# brushless_motorshield_v1.net
KiCad netlist of a schematic drawn in EAGLE
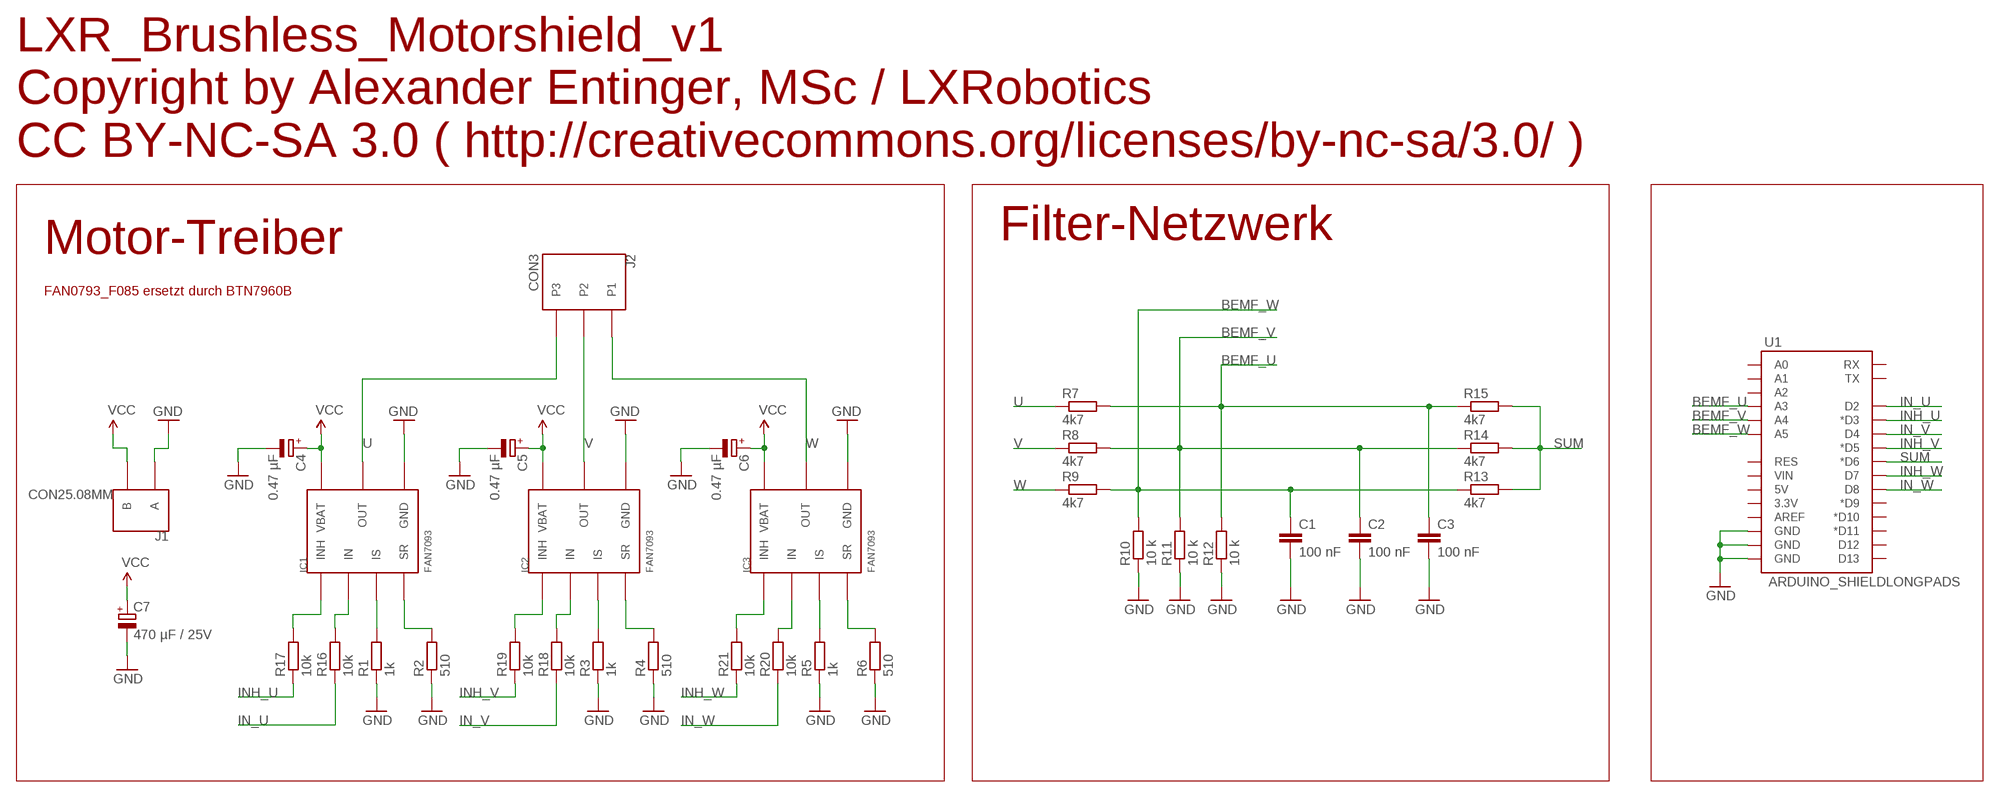
[diagram p0: schematic, sheet 1]

(export (version "E")
  (design (tool "Eeschema 10.0.6"))
  (components
    (comp (ref "C1")
      (value "100 nF")
      (footprint "eagle-import:C0805")
      (libsource (lib "eagle-import") (part "C-EUC0805"))
    )
    (comp (ref "C2")
      (value "100 nF")
      (footprint "eagle-import:C0805")
      (libsource (lib "eagle-import") (part "C-EUC0805"))
    )
    (comp (ref "C3")
      (value "100 nF")
      (footprint "eagle-import:C0805")
      (libsource (lib "eagle-import") (part "C-EUC0805"))
    )
    (comp (ref "C4")
      (value "0.47 µF")
      (footprint "eagle-import:KEMET_A")
      (libsource (lib "eagle-import") (part "CPOL-EU"))
    )
    (comp (ref "C5")
      (value "0.47 µF")
      (footprint "eagle-import:KEMET_A")
      (libsource (lib "eagle-import") (part "CPOL-EU"))
    )
    (comp (ref "C6")
      (value "0.47 µF")
      (footprint "eagle-import:KEMET_A")
      (libsource (lib "eagle-import") (part "CPOL-EU"))
    )
    (comp (ref "C7")
      (value "470 µF / 25V")
      (footprint "eagle-import:E5-10,5")
      (libsource (lib "eagle-import") (part "CPOL-EUE5-10.5"))
    )
    (comp (ref "IC1")
      (value "FAN7093")
      (footprint "eagle-import:TO263-7L")
      (libsource (lib "eagle-import") (part "FAN7093"))
    )
    (comp (ref "IC2")
      (value "FAN7093")
      (footprint "eagle-import:TO263-7L")
      (libsource (lib "eagle-import") (part "FAN7093"))
    )
    (comp (ref "IC3")
      (value "FAN7093")
      (footprint "eagle-import:TO263-7L")
      (libsource (lib "eagle-import") (part "FAN7093"))
    )
    (comp (ref "J1")
      (value "CON25.08MM")
      (footprint "eagle-import:CON2_SCHRAUBKLEMME")
      (libsource (lib "eagle-import") (part "CON25.08MM"))
    )
    (comp (ref "J2")
      (value "CON3")
      (footprint "eagle-import:CON3_SCHRAUBKLEMME")
      (libsource (lib "eagle-import") (part "CON3"))
    )
    (comp (ref "R1")
      (value "1k")
      (footprint "eagle-import:R0805")
      (libsource (lib "eagle-import") (part "R-EU_R0805"))
    )
    (comp (ref "R2")
      (value "510")
      (footprint "eagle-import:R0805")
      (libsource (lib "eagle-import") (part "R-EU_R0805"))
    )
    (comp (ref "R3")
      (value "1k")
      (footprint "eagle-import:R0805")
      (libsource (lib "eagle-import") (part "R-EU_R0805"))
    )
    (comp (ref "R4")
      (value "510")
      (footprint "eagle-import:R0805")
      (libsource (lib "eagle-import") (part "R-EU_R0805"))
    )
    (comp (ref "R5")
      (value "1k")
      (footprint "eagle-import:R0805")
      (libsource (lib "eagle-import") (part "R-EU_R0805"))
    )
    (comp (ref "R6")
      (value "510")
      (footprint "eagle-import:R0805")
      (libsource (lib "eagle-import") (part "R-EU_R0805"))
    )
    (comp (ref "R7")
      (value "4k7")
      (footprint "eagle-import:R0805")
      (libsource (lib "eagle-import") (part "R-EU_R0805"))
    )
    (comp (ref "R8")
      (value "4k7")
      (footprint "eagle-import:R0805")
      (libsource (lib "eagle-import") (part "R-EU_R0805"))
    )
    (comp (ref "R9")
      (value "4k7")
      (footprint "eagle-import:R0805")
      (libsource (lib "eagle-import") (part "R-EU_R0805"))
    )
    (comp (ref "R10")
      (value "10 k")
      (footprint "eagle-import:R0805")
      (libsource (lib "eagle-import") (part "R-EU_R0805"))
    )
    (comp (ref "R11")
      (value "10 k")
      (footprint "eagle-import:R0805")
      (libsource (lib "eagle-import") (part "R-EU_R0805"))
    )
    (comp (ref "R12")
      (value "10 k")
      (footprint "eagle-import:R0805")
      (libsource (lib "eagle-import") (part "R-EU_R0805"))
    )
    (comp (ref "R13")
      (value "4k7")
      (footprint "eagle-import:R0805")
      (libsource (lib "eagle-import") (part "R-EU_R0805"))
    )
    (comp (ref "R14")
      (value "4k7")
      (footprint "eagle-import:R0805")
      (libsource (lib "eagle-import") (part "R-EU_R0805"))
    )
    (comp (ref "R15")
      (value "4k7")
      (footprint "eagle-import:R0805")
      (libsource (lib "eagle-import") (part "R-EU_R0805"))
    )
    (comp (ref "R16")
      (value "10k")
      (footprint "eagle-import:R0805")
      (libsource (lib "eagle-import") (part "R-EU_R0805"))
    )
    (comp (ref "R17")
      (value "10k")
      (footprint "eagle-import:R0805")
      (libsource (lib "eagle-import") (part "R-EU_R0805"))
    )
    (comp (ref "R18")
      (value "10k")
      (footprint "eagle-import:R0805")
      (libsource (lib "eagle-import") (part "R-EU_R0805"))
    )
    (comp (ref "R19")
      (value "10k")
      (footprint "eagle-import:R0805")
      (libsource (lib "eagle-import") (part "R-EU_R0805"))
    )
    (comp (ref "R20")
      (value "10k")
      (footprint "eagle-import:R0805")
      (libsource (lib "eagle-import") (part "R-EU_R0805"))
    )
    (comp (ref "R21")
      (value "10k")
      (footprint "eagle-import:R0805")
      (libsource (lib "eagle-import") (part "R-EU_R0805"))
    )
    (comp (ref "U1")
      (value "ARDUINO_SHIELDLONGPADS")
      (footprint "eagle-import:DUEMILANOVE_SHIELD_LONGPADS")
      (libsource (lib "eagle-import") (part "ARDUINO_SHIELDLONGPADS"))
    )
  )
  (nets
    (net (code "1") (name "/BEMF_U") (class "Default")
      (node (ref "C3") (pin "1") (pinfunction "1_1") (pintype "passive"))
      (node (ref "R12") (pin "2") (pinfunction "2_2") (pintype "passive"))
      (node (ref "R15") (pin "1") (pinfunction "1_1") (pintype "passive"))
      (node (ref "R7") (pin "2") (pinfunction "2_2") (pintype "passive"))
      (node (ref "U1") (pin "A3") (pinfunction "A3_A3") (pintype "bidirectional"))
    )
    (net (code "2") (name "/BEMF_V") (class "Default")
      (node (ref "C2") (pin "1") (pinfunction "1_1") (pintype "passive"))
      (node (ref "R11") (pin "2") (pinfunction "2_2") (pintype "passive"))
      (node (ref "R14") (pin "1") (pinfunction "1_1") (pintype "passive"))
      (node (ref "R8") (pin "2") (pinfunction "2_2") (pintype "passive"))
      (node (ref "U1") (pin "A4") (pinfunction "A4_A4") (pintype "bidirectional"))
    )
    (net (code "3") (name "/BEMF_W") (class "Default")
      (node (ref "C1") (pin "1") (pinfunction "1_1") (pintype "passive"))
      (node (ref "R10") (pin "2") (pinfunction "2_2") (pintype "passive"))
      (node (ref "R13") (pin "1") (pinfunction "1_1") (pintype "passive"))
      (node (ref "R9") (pin "2") (pinfunction "2_2") (pintype "passive"))
      (node (ref "U1") (pin "A5") (pinfunction "A5_A5") (pintype "bidirectional"))
    )
    (net (code "4") (name "/INH_U") (class "Default")
      (node (ref "R17") (pin "1") (pinfunction "1_1") (pintype "passive"))
      (node (ref "U1") (pin "D3") (pinfunction "*D3_D3") (pintype "bidirectional"))
    )
    (net (code "5") (name "/INH_V") (class "Default")
      (node (ref "R19") (pin "1") (pinfunction "1_1") (pintype "passive"))
      (node (ref "U1") (pin "D5") (pinfunction "*D5_D5") (pintype "bidirectional"))
    )
    (net (code "6") (name "/INH_W") (class "Default")
      (node (ref "R21") (pin "1") (pinfunction "1_1") (pintype "passive"))
      (node (ref "U1") (pin "D7") (pinfunction "D7_D7") (pintype "bidirectional"))
    )
    (net (code "7") (name "/IN_U") (class "Default")
      (node (ref "R16") (pin "1") (pinfunction "1_1") (pintype "passive"))
      (node (ref "U1") (pin "D2") (pinfunction "D2_D2") (pintype "bidirectional"))
    )
    (net (code "8") (name "/IN_V") (class "Default")
      (node (ref "R18") (pin "1") (pinfunction "1_1") (pintype "passive"))
      (node (ref "U1") (pin "D4") (pinfunction "D4_D4") (pintype "bidirectional"))
    )
    (net (code "9") (name "/IN_W") (class "Default")
      (node (ref "R20") (pin "1") (pinfunction "1_1") (pintype "passive"))
      (node (ref "U1") (pin "D8") (pinfunction "D8_D8") (pintype "bidirectional"))
    )
    (net (code "10") (name "/SUM") (class "Default")
      (node (ref "R13") (pin "2") (pinfunction "2_2") (pintype "passive"))
      (node (ref "R14") (pin "2") (pinfunction "2_2") (pintype "passive"))
      (node (ref "R15") (pin "2") (pinfunction "2_2") (pintype "passive"))
      (node (ref "U1") (pin "D6") (pinfunction "*D6_D6") (pintype "bidirectional"))
    )
    (net (code "11") (name "/U") (class "Default")
      (node (ref "IC1") (pin "OUT") (pinfunction "OUT_OUT") (pintype "bidirectional"))
      (node (ref "IC1") (pin "OUT@1") (pinfunction "OUT_OUT@1") (pintype "bidirectional"))
      (node (ref "J2") (pin "P3") (pinfunction "P3_P3") (pintype "bidirectional"))
      (node (ref "R7") (pin "1") (pinfunction "1_1") (pintype "passive"))
    )
    (net (code "12") (name "/V") (class "Default")
      (node (ref "IC2") (pin "OUT") (pinfunction "OUT_OUT") (pintype "bidirectional"))
      (node (ref "IC2") (pin "OUT@1") (pinfunction "OUT_OUT@1") (pintype "bidirectional"))
      (node (ref "J2") (pin "P2") (pinfunction "P2_P2") (pintype "bidirectional"))
      (node (ref "R8") (pin "1") (pinfunction "1_1") (pintype "passive"))
    )
    (net (code "13") (name "/W") (class "Default")
      (node (ref "IC3") (pin "OUT") (pinfunction "OUT_OUT") (pintype "bidirectional"))
      (node (ref "IC3") (pin "OUT@1") (pinfunction "OUT_OUT@1") (pintype "bidirectional"))
      (node (ref "J2") (pin "P1") (pinfunction "P1_P1") (pintype "bidirectional"))
      (node (ref "R9") (pin "1") (pinfunction "1_1") (pintype "passive"))
    )
    (net (code "14") (name "GND") (class "Default")
      (node (ref "C1") (pin "2") (pinfunction "2_2") (pintype "passive"))
      (node (ref "C2") (pin "2") (pinfunction "2_2") (pintype "passive"))
      (node (ref "C3") (pin "2") (pinfunction "2_2") (pintype "passive"))
      (node (ref "C4") (pin "CATHODE") (pinfunction "-_CATHODE") (pintype "passive"))
      (node (ref "C5") (pin "CATHODE") (pinfunction "-_CATHODE") (pintype "passive"))
      (node (ref "C6") (pin "CATHODE") (pinfunction "-_CATHODE") (pintype "passive"))
      (node (ref "C7") (pin "-") (pinfunction "-_-") (pintype "passive"))
      (node (ref "IC1") (pin "GND") (pinfunction "GND_GND") (pintype "bidirectional"))
      (node (ref "IC2") (pin "GND") (pinfunction "GND_GND") (pintype "bidirectional"))
      (node (ref "IC3") (pin "GND") (pinfunction "GND_GND") (pintype "bidirectional"))
      (node (ref "J1") (pin "1") (pinfunction "A_1") (pintype "bidirectional"))
      (node (ref "R1") (pin "1") (pinfunction "1_1") (pintype "passive"))
      (node (ref "R10") (pin "1") (pinfunction "1_1") (pintype "passive"))
      (node (ref "R11") (pin "1") (pinfunction "1_1") (pintype "passive"))
      (node (ref "R12") (pin "1") (pinfunction "1_1") (pintype "passive"))
      (node (ref "R2") (pin "1") (pinfunction "1_1") (pintype "passive"))
      (node (ref "R3") (pin "1") (pinfunction "1_1") (pintype "passive"))
      (node (ref "R4") (pin "1") (pinfunction "1_1") (pintype "passive"))
      (node (ref "R5") (pin "1") (pinfunction "1_1") (pintype "passive"))
      (node (ref "R6") (pin "1") (pinfunction "1_1") (pintype "passive"))
      (node (ref "U1") (pin "GND@0") (pinfunction "GND_GND@0") (pintype "bidirectional"))
      (node (ref "U1") (pin "GND@1") (pinfunction "GND_GND@1") (pintype "bidirectional"))
      (node (ref "U1") (pin "GND@2") (pinfunction "GND_GND@2") (pintype "bidirectional"))
    )
    (net (code "15") (name "Net-(IC1-PadIN)") (class "Default")
      (node (ref "IC1") (pin "IN") (pinfunction "IN_IN") (pintype "bidirectional"))
      (node (ref "R16") (pin "2") (pinfunction "2_2") (pintype "passive"))
    )
    (net (code "16") (name "Net-(IC1-PadINH)") (class "Default")
      (node (ref "IC1") (pin "INH") (pinfunction "INH_INH") (pintype "bidirectional"))
      (node (ref "R17") (pin "2") (pinfunction "2_2") (pintype "passive"))
    )
    (net (code "17") (name "Net-(IC1-PadIS)") (class "Default")
      (node (ref "IC1") (pin "IS") (pinfunction "IS_IS") (pintype "bidirectional"))
      (node (ref "R1") (pin "2") (pinfunction "2_2") (pintype "passive"))
    )
    (net (code "18") (name "Net-(IC1-PadSR)") (class "Default")
      (node (ref "IC1") (pin "SR") (pinfunction "SR_SR") (pintype "bidirectional"))
      (node (ref "R2") (pin "2") (pinfunction "2_2") (pintype "passive"))
    )
    (net (code "19") (name "Net-(IC2-PadIN)") (class "Default")
      (node (ref "IC2") (pin "IN") (pinfunction "IN_IN") (pintype "bidirectional"))
      (node (ref "R18") (pin "2") (pinfunction "2_2") (pintype "passive"))
    )
    (net (code "20") (name "Net-(IC2-PadINH)") (class "Default")
      (node (ref "IC2") (pin "INH") (pinfunction "INH_INH") (pintype "bidirectional"))
      (node (ref "R19") (pin "2") (pinfunction "2_2") (pintype "passive"))
    )
    (net (code "21") (name "Net-(IC2-PadIS)") (class "Default")
      (node (ref "IC2") (pin "IS") (pinfunction "IS_IS") (pintype "bidirectional"))
      (node (ref "R3") (pin "2") (pinfunction "2_2") (pintype "passive"))
    )
    (net (code "22") (name "Net-(IC2-PadSR)") (class "Default")
      (node (ref "IC2") (pin "SR") (pinfunction "SR_SR") (pintype "bidirectional"))
      (node (ref "R4") (pin "2") (pinfunction "2_2") (pintype "passive"))
    )
    (net (code "23") (name "Net-(IC3-PadIN)") (class "Default")
      (node (ref "IC3") (pin "IN") (pinfunction "IN_IN") (pintype "bidirectional"))
      (node (ref "R20") (pin "2") (pinfunction "2_2") (pintype "passive"))
    )
    (net (code "24") (name "Net-(IC3-PadINH)") (class "Default")
      (node (ref "IC3") (pin "INH") (pinfunction "INH_INH") (pintype "bidirectional"))
      (node (ref "R21") (pin "2") (pinfunction "2_2") (pintype "passive"))
    )
    (net (code "25") (name "Net-(IC3-PadIS)") (class "Default")
      (node (ref "IC3") (pin "IS") (pinfunction "IS_IS") (pintype "bidirectional"))
      (node (ref "R5") (pin "2") (pinfunction "2_2") (pintype "passive"))
    )
    (net (code "26") (name "Net-(IC3-PadSR)") (class "Default")
      (node (ref "IC3") (pin "SR") (pinfunction "SR_SR") (pintype "bidirectional"))
      (node (ref "R6") (pin "2") (pinfunction "2_2") (pintype "passive"))
    )
    (net (code "27") (name "VCC") (class "Default")
      (node (ref "C4") (pin "ANODE") (pinfunction "+_ANODE") (pintype "passive"))
      (node (ref "C5") (pin "ANODE") (pinfunction "+_ANODE") (pintype "passive"))
      (node (ref "C6") (pin "ANODE") (pinfunction "+_ANODE") (pintype "passive"))
      (node (ref "C7") (pin "+") (pinfunction "+_+") (pintype "passive"))
      (node (ref "IC1") (pin "VBATT") (pinfunction "VBAT_VBATT") (pintype "bidirectional"))
      (node (ref "IC2") (pin "VBATT") (pinfunction "VBAT_VBATT") (pintype "bidirectional"))
      (node (ref "IC3") (pin "VBATT") (pinfunction "VBAT_VBATT") (pintype "bidirectional"))
      (node (ref "J1") (pin "2") (pinfunction "B_2") (pintype "bidirectional"))
    )
    (net (code "28") (name "unconnected-(U1-*D9-PadD9)") (class "Default")
      (node (ref "U1") (pin "D9") (pinfunction "*D9_D9") (pintype "bidirectional"))
    )
    (net (code "29") (name "unconnected-(U1-*D10-PadD10)") (class "Default")
      (node (ref "U1") (pin "D10") (pinfunction "*D10_D10") (pintype "bidirectional"))
    )
    (net (code "30") (name "unconnected-(U1-*D11-PadD11)") (class "Default")
      (node (ref "U1") (pin "D11") (pinfunction "*D11_D11") (pintype "bidirectional"))
    )
    (net (code "31") (name "unconnected-(U1-Pad3.3V)") (class "Default")
      (node (ref "U1") (pin "3.3V") (pinfunction "3.3V_3.3V") (pintype "bidirectional"))
    )
    (net (code "32") (name "unconnected-(U1-Pad5V)") (class "Default")
      (node (ref "U1") (pin "5V") (pinfunction "5V_5V") (pintype "bidirectional"))
    )
    (net (code "33") (name "unconnected-(U1-PadA0)") (class "Default")
      (node (ref "U1") (pin "A0") (pinfunction "A0_A0") (pintype "bidirectional"))
    )
    (net (code "34") (name "unconnected-(U1-PadA1)") (class "Default")
      (node (ref "U1") (pin "A1") (pinfunction "A1_A1") (pintype "bidirectional"))
    )
    (net (code "35") (name "unconnected-(U1-PadA2)") (class "Default")
      (node (ref "U1") (pin "A2") (pinfunction "A2_A2") (pintype "bidirectional"))
    )
    (net (code "36") (name "unconnected-(U1-PadAREF)") (class "Default")
      (node (ref "U1") (pin "AREF") (pinfunction "AREF_AREF") (pintype "bidirectional"))
    )
    (net (code "37") (name "unconnected-(U1-PadD12)") (class "Default")
      (node (ref "U1") (pin "D12") (pinfunction "D12_D12") (pintype "bidirectional"))
    )
    (net (code "38") (name "unconnected-(U1-PadD13)") (class "Default")
      (node (ref "U1") (pin "D13") (pinfunction "D13_D13") (pintype "bidirectional"))
    )
    (net (code "39") (name "unconnected-(U1-PadRES)") (class "Default")
      (node (ref "U1") (pin "RES") (pinfunction "RES_RES") (pintype "bidirectional"))
    )
    (net (code "40") (name "unconnected-(U1-PadRX)") (class "Default")
      (node (ref "U1") (pin "RX") (pinfunction "RX_RX") (pintype "bidirectional"))
    )
    (net (code "41") (name "unconnected-(U1-PadTX)") (class "Default")
      (node (ref "U1") (pin "TX") (pinfunction "TX_TX") (pintype "bidirectional"))
    )
    (net (code "42") (name "unconnected-(U1-PadVIN)") (class "Default")
      (node (ref "U1") (pin "VIN") (pinfunction "VIN_VIN") (pintype "bidirectional"))
    )
  )
)
